# AirScout_SchematicsV2_0.net
KiCad netlist of a schematic drawn in Altium Designer
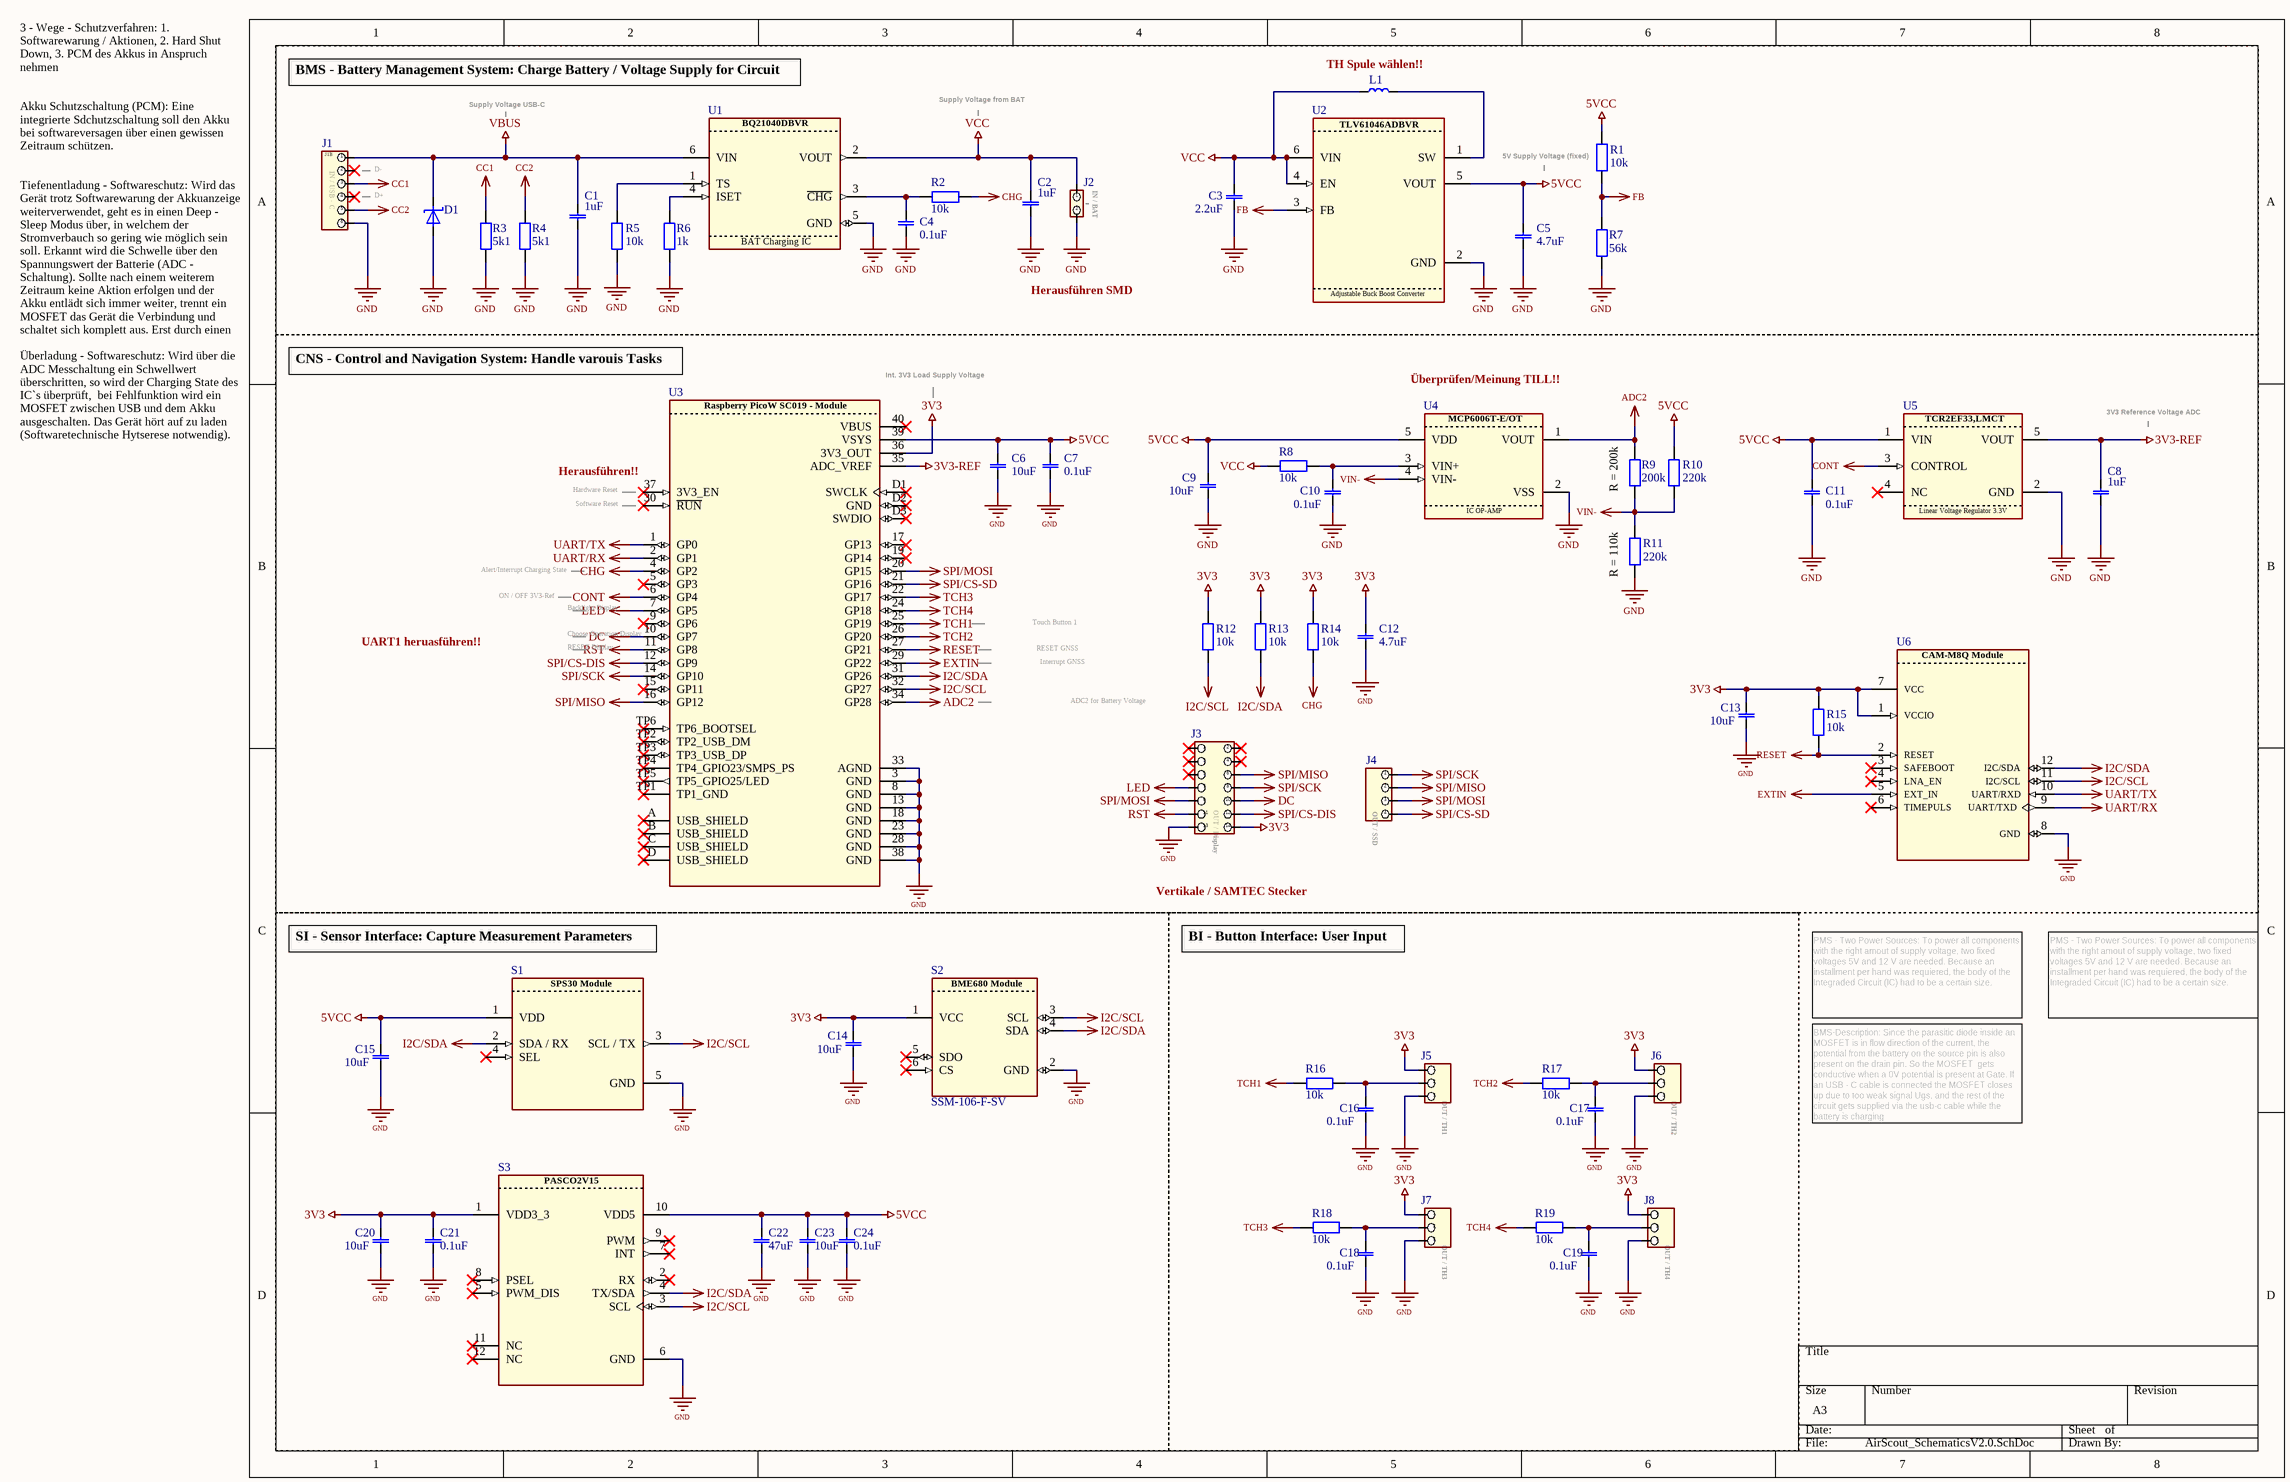
[diagram p0: AirScout_SchematicsV2.0.SchDoc]

(export (version "E")
  (design (tool "Eeschema 10.0.6"))
  (components
    (comp (ref "C1")
      (value "1uF")
      (footprint "CAPC340180_140N_KEM")
      (description "CAP CER 1UF 25V X7R 1206")
      (fields (field (name "Comment") "C1206C105K3RACTU"))
      (libsource (lib "AirScoutSchLibV2.0") (part "CAP"))
    )
    (comp (ref "C2")
      (value "1uF")
      (footprint "CAPC340180_140N_KEM")
      (description "CAP CER 1UF 25V X7R 1206")
      (fields (field (name "Comment") "C1206C105K3RACTU"))
      (libsource (lib "AirScoutSchLibV2.0") (part "CAP"))
    )
    (comp (ref "C3")
      (value "2.2uF")
      (footprint "CAPC340180_140N_KEM")
      (description "CAP CER 2.2UF 50V X7R 1206")
      (fields (field (name "Comment") "CL31B225KBHNNNE"))
      (libsource (lib "AirScoutSchLibV2.0") (part "CAP"))
    )
    (comp (ref "C4")
      (value "0.1uF")
      (footprint "CAPC340180_140N_KEM")
      (description "CAP CER 0.1UF 50V X7R 1206")
      (fields (field (name "Comment") "C1206C104K5RACTU"))
      (libsource (lib "AirScoutSchLibV2.0") (part "CAP"))
    )
    (comp (ref "C5")
      (value "4.7uF")
      (footprint "CAPC340180_140N_KEM")
      (description "CAP CER 4.7UF 50V X7R 1206")
      (fields (field (name "Comment") "CL31B475KBHNFNE"))
      (libsource (lib "AirScoutSchLibV2.0") (part "CAP"))
    )
    (comp (ref "C6")
      (value "10uF")
      (footprint "CAPC340180_140N_KEM")
      (description "CAP CER 10UF 25V X7R 1206")
      (fields (field (name "Comment") "CL31B106KAHNNNE"))
      (libsource (lib "AirScoutSchLibV2.0") (part "CAP"))
    )
    (comp (ref "C7")
      (value "0.1uF")
      (footprint "CAPC340180_140N_KEM")
      (description "CAP CER 0.1UF 50V X7R 1206")
      (fields (field (name "Comment") "C1206C104K5RACTU"))
      (libsource (lib "AirScoutSchLibV2.0") (part "CAP"))
    )
    (comp (ref "C8")
      (value "1uF")
      (footprint "CAPC340180_140N_KEM")
      (description "CAP CER 1UF 25V X7R 1206")
      (fields (field (name "Comment") "C1206C105K3RACTU"))
      (libsource (lib "AirScoutSchLibV2.0") (part "CAP"))
    )
    (comp (ref "C9")
      (value "10uF")
      (footprint "CAPC340180_140N_KEM")
      (description "CAP CER 10UF 25V X7R 1206")
      (fields (field (name "Comment") "CL31B106KAHNNNE"))
      (libsource (lib "AirScoutSchLibV2.0") (part "CAP"))
    )
    (comp (ref "C10")
      (value "0.1uF")
      (footprint "CAPC340180_140N_KEM")
      (description "CAP CER 0.1UF 50V X7R 1206")
      (fields (field (name "Comment") "C1206C104K5RACTU"))
      (libsource (lib "AirScoutSchLibV2.0") (part "CAP"))
    )
    (comp (ref "C11")
      (value "0.1uF")
      (footprint "CAPC340180_140N_KEM")
      (description "CAP CER 0.1UF 50V X7R 1206")
      (fields (field (name "Comment") "C1206C104K5RACTU"))
      (libsource (lib "AirScoutSchLibV2.0") (part "CAP"))
    )
    (comp (ref "C12")
      (value "4.7uF")
      (footprint "CAPC340180_140N_KEM")
      (description "CAP CER 4.7UF 50V X7R 1206")
      (fields (field (name "Comment") "CL31B475KBHNFNE"))
      (libsource (lib "AirScoutSchLibV2.0") (part "CAP"))
    )
    (comp (ref "C13")
      (value "10uF")
      (footprint "CAPC340180_140N_KEM")
      (description "CAP CER 10UF 25V X7R 1206")
      (fields (field (name "Comment") "CL31B106KAHNNNE"))
      (libsource (lib "AirScoutSchLibV2.0") (part "CAP"))
    )
    (comp (ref "C14")
      (value "10uF")
      (footprint "CAPC340180_140N_KEM")
      (description "CAP CER 10UF 25V X7R 1206")
      (fields (field (name "Comment") "CL31B106KAHNNNE"))
      (libsource (lib "AirScoutSchLibV2.0") (part "CAP"))
    )
    (comp (ref "C15")
      (value "10uF")
      (footprint "CAPC340180_140N_KEM")
      (description "CAP CER 10UF 25V X7R 1206")
      (fields (field (name "Comment") "CL31B106KAHNNNE"))
      (libsource (lib "AirScoutSchLibV2.0") (part "CAP"))
    )
    (comp (ref "C16")
      (value "0.1uF")
      (footprint "CAPC340180_140N_KEM")
      (description "CAP CER 0.1UF 50V X7R 1206")
      (fields (field (name "Comment") "C1206C104K5RACTU"))
      (libsource (lib "AirScoutSchLibV2.0") (part "CAP"))
    )
    (comp (ref "C17")
      (value "0.1uF")
      (footprint "CAPC340180_140N_KEM")
      (description "CAP CER 0.1UF 50V X7R 1206")
      (fields (field (name "Comment") "C1206C104K5RACTU"))
      (libsource (lib "AirScoutSchLibV2.0") (part "CAP"))
    )
    (comp (ref "C18")
      (value "0.1uF")
      (footprint "CAPC340180_140N_KEM")
      (description "CAP CER 0.1UF 50V X7R 1206")
      (fields (field (name "Comment") "C1206C104K5RACTU"))
      (libsource (lib "AirScoutSchLibV2.0") (part "CAP"))
    )
    (comp (ref "C19")
      (value "0.1uF")
      (footprint "CAPC340180_140N_KEM")
      (description "CAP CER 0.1UF 50V X7R 1206")
      (fields (field (name "Comment") "C1206C104K5RACTU"))
      (libsource (lib "AirScoutSchLibV2.0") (part "CAP"))
    )
    (comp (ref "C20")
      (value "10uF")
      (footprint "CAPC340180_140N_KEM")
      (description "CAP CER 10UF 25V X7R 1206")
      (fields (field (name "Comment") "CL31B106KAHNNNE"))
      (libsource (lib "AirScoutSchLibV2.0") (part "CAP"))
    )
    (comp (ref "C21")
      (value "0.1uF")
      (footprint "CAPC340180_140N_KEM")
      (description "CAP CER 0.1UF 50V X7R 1206")
      (fields (field (name "Comment") "C1206C104K5RACTU"))
      (libsource (lib "AirScoutSchLibV2.0") (part "CAP"))
    )
    (comp (ref "C22")
      (value "47uF")
      (footprint "CAPC340180_140N_KEM")
      (description "CAP CER 47UF 6.3V X5R 1206")
      (fields (field (name "Comment") "CL31A476MQHNNNE"))
      (libsource (lib "AirScoutSchLibV2.0") (part "CAP"))
    )
    (comp (ref "C23")
      (value "10uF")
      (footprint "CAPC340180_140N_KEM")
      (description "CAP CER 10UF 25V X7R 1206")
      (fields (field (name "Comment") "CL31B106KAHNNNE"))
      (libsource (lib "AirScoutSchLibV2.0") (part "CAP"))
    )
    (comp (ref "C24")
      (value "0.1uF")
      (footprint "CAPC340180_140N_KEM")
      (description "CAP CER 0.1UF 50V X7R 1206")
      (fields (field (name "Comment") "C1206C104K5RACTU"))
      (libsource (lib "AirScoutSchLibV2.0") (part "CAP"))
    )
    (comp (ref "D1")
      (value "SMBJ14CA-13-F")
      (footprint "SMB_DIO")
      (description "TVS DIODE 14VWM 23.2VC SMB")
      (libsource (lib "AirScoutSchLibV2.0") (part "Diode-Schottky"))
    )
    (comp (ref "J1")
      (value "B6B-PH-K-S")
      (footprint "JST_B6B-PH-K-S")
      (description "CONN HEADER VERT 6POS 2MM")
      (libsource (lib "AirScoutSchLibV2.0") (part "CON6x1"))
    )
    (comp (ref "J2")
      (value "B02B-PASK-1")
      (footprint "JST_B2B-PH-K-S")
      (description "CONN HEADER VERT 2POS 2MM")
      (libsource (lib "AirScoutSchLibV2.0") (part "CON2x1_vertical"))
    )
    (comp (ref "J3")
      (value "0705430013")
      (footprint "CONN_14POL_SAMTEC")
      (description "CONN HEADER VERT 14POS 2.54MM")
      (libsource (lib "AirScoutSchLibV2.0") (part "CON7x2"))
    )
    (comp (ref "J4")
      (value "4x1 vertical Connector Box")
      (footprint "JST_B4B-XH-A")
      (description "Can be used to create connectivity between two plates with cables or similar.")
      (libsource (lib "AirScoutSchLibV2.0") (part "CON 4x1"))
    )
    (comp (ref "J5")
      (value "0705430002")
      (footprint "CONN_3POL_SAMTEC")
      (description "CONN HEADER VERT 3POS 2.54MM")
      (libsource (lib "AirScoutSchLibV2.0") (part "CON 3x1"))
    )
    (comp (ref "J6")
      (value "0705430002")
      (footprint "CONN_3POL_SAMTEC")
      (description "CONN HEADER VERT 3POS 2.54MM")
      (libsource (lib "AirScoutSchLibV2.0") (part "CON 3x1"))
    )
    (comp (ref "J7")
      (value "0705430002")
      (footprint "CONN_3POL_SAMTEC")
      (description "CONN HEADER VERT 3POS 2.54MM")
      (libsource (lib "AirScoutSchLibV2.0") (part "CON 3x1"))
    )
    (comp (ref "J8")
      (value "0705430002")
      (footprint "CONN_3POL_SAMTEC")
      (description "CONN HEADER VERT 3POS 2.54MM")
      (libsource (lib "AirScoutSchLibV2.0") (part "CON 3x1"))
    )
    (comp (ref "L1")
      (value "PA4332.103NLT")
      (footprint "IND_FDSD0420-H-100M=P3")
      (description "FIXED IND 10UH 2A 216 MOHM SMD; \r\nAIUR-05-100K")
      (libsource (lib "AirScoutSchLibV2.0") (part "Inductor"))
    )
    (comp (ref "R1")
      (value "10k")
      (footprint "RESC3116X65N")
      (description "RES 10K OHM 1% 1/4W 1206")
      (fields (field (name "Comment") "RC1206FR-0710KL"))
      (libsource (lib "AirScoutSchLibV2.0") (part "RES"))
    )
    (comp (ref "R2")
      (value "10k")
      (footprint "RESC3116X65N")
      (description "RES 10K OHM 1% 1/4W 1206")
      (fields (field (name "Comment") "RC1206FR-0710KL"))
      (libsource (lib "AirScoutSchLibV2.0") (part "RES"))
    )
    (comp (ref "R3")
      (value "5k1")
      (footprint "RESC3116X65N")
      (description "RES 5.1K OHM 5% 1/4W 1206")
      (fields (field (name "Comment") "RMCF1206JT5K10"))
      (libsource (lib "AirScoutSchLibV2.0") (part "RES"))
    )
    (comp (ref "R4")
      (value "5k1")
      (footprint "RESC3116X65N")
      (description "RES 5.1K OHM 5% 1/4W 1206")
      (fields (field (name "Comment") "RMCF1206JT5K10"))
      (libsource (lib "AirScoutSchLibV2.0") (part "RES"))
    )
    (comp (ref "R5")
      (value "10k")
      (footprint "RESC3116X65N")
      (description "RES 10K OHM 1% 1/4W 1206")
      (fields (field (name "Comment") "RC1206FR-0710KL"))
      (libsource (lib "AirScoutSchLibV2.0") (part "RES"))
    )
    (comp (ref "R6")
      (value "1k")
      (footprint "RESC3116X65N")
      (description "RES 1K OHM 1% 1/2W 1206")
      (fields (field (name "Comment") "RNCP1206FTD1K00"))
      (libsource (lib "AirScoutSchLibV2.0") (part "RES"))
    )
    (comp (ref "R7")
      (value "56k")
      (footprint "RESC3116X65N")
      (description "RES 56K OHM 5% 1/4W 1206")
      (fields (field (name "Comment") "RMCF1206JT56K0"))
      (libsource (lib "AirScoutSchLibV2.0") (part "RES"))
    )
    (comp (ref "R8")
      (value "10k")
      (footprint "RESC3116X65N")
      (description "RES 10K OHM 1% 1/4W 1206")
      (fields (field (name "Comment") "RC1206FR-0710KL"))
      (libsource (lib "AirScoutSchLibV2.0") (part "RES"))
    )
    (comp (ref "R9")
      (value "200k")
      (footprint "RESC3116X65N")
      (description "RES 200K OHM 5% 1/4W 1206")
      (fields (field (name "Comment") "RC1206JR-07200KL"))
      (libsource (lib "AirScoutSchLibV2.0") (part "RES"))
    )
    (comp (ref "R10")
      (value "220k")
      (footprint "RESC3116X65N")
      (description "RES 220K OHM 5% 1/4W 1206")
      (fields (field (name "Comment") "RC1206JR-07220KL"))
      (libsource (lib "AirScoutSchLibV2.0") (part "RES"))
    )
    (comp (ref "R11")
      (value "220k")
      (footprint "RESC3116X65N")
      (description "RES 220K OHM 5% 1/4W 1206")
      (fields (field (name "Comment") "RC1206JR-07220KL"))
      (libsource (lib "AirScoutSchLibV2.0") (part "RES"))
    )
    (comp (ref "R12")
      (value "10k")
      (footprint "RESC3116X65N")
      (description "RES 10K OHM 1% 1/4W 1206")
      (fields (field (name "Comment") "RC1206FR-0710KL"))
      (libsource (lib "AirScoutSchLibV2.0") (part "RES"))
    )
    (comp (ref "R13")
      (value "10k")
      (footprint "RESC3116X65N")
      (description "RES 10K OHM 1% 1/4W 1206")
      (fields (field (name "Comment") "RC1206FR-0710KL"))
      (libsource (lib "AirScoutSchLibV2.0") (part "RES"))
    )
    (comp (ref "R14")
      (value "10k")
      (footprint "RESC3116X65N")
      (description "RES 10K OHM 1% 1/4W 1206")
      (fields (field (name "Comment") "RC1206FR-0710KL"))
      (libsource (lib "AirScoutSchLibV2.0") (part "RES"))
    )
    (comp (ref "R15")
      (value "10k")
      (footprint "RESC3116X65N")
      (description "RES 10K OHM 1% 1/4W 1206")
      (fields (field (name "Comment") "RC1206FR-0710KL"))
      (libsource (lib "AirScoutSchLibV2.0") (part "RES"))
    )
    (comp (ref "R16")
      (value "10k")
      (footprint "RESC3116X65N")
      (description "RES 10K OHM 1% 1/4W 1206")
      (fields (field (name "Comment") "RC1206FR-0710KL"))
      (libsource (lib "AirScoutSchLibV2.0") (part "RES"))
    )
    (comp (ref "R17")
      (value "10k")
      (footprint "RESC3116X65N")
      (description "RES 10K OHM 1% 1/4W 1206")
      (fields (field (name "Comment") "RC1206FR-0710KL"))
      (libsource (lib "AirScoutSchLibV2.0") (part "RES"))
    )
    (comp (ref "R18")
      (value "10k")
      (footprint "RESC3116X65N")
      (description "RES 10K OHM 1% 1/4W 1206")
      (fields (field (name "Comment") "RC1206FR-0710KL"))
      (libsource (lib "AirScoutSchLibV2.0") (part "RES"))
    )
    (comp (ref "R19")
      (value "10k")
      (footprint "RESC3116X65N")
      (description "RES 10K OHM 1% 1/4W 1206")
      (fields (field (name "Comment") "RC1206FR-0710KL"))
      (libsource (lib "AirScoutSchLibV2.0") (part "RES"))
    )
    (comp (ref "S1")
      (value "B5B-ZR")
      (footprint "CONN5_B5B-ZR_JST")
      (description "Plug: CONN HEADER VERT 5POS 1.5MM; Air Sensor Dust Sensor Box SPS30 Module: 1649-1106-ND")
      (libsource (lib "AirScoutSchLibV2.0") (part "SPS30 Module"))
    )
    (comp (ref "S2")
      (value "SSM-106-F-SV")
      (footprint "PIM357")
      (libsource (lib "AirScoutSchLibV2.0") (part "BME680 Module"))
    )
    (comp (ref "S3")
      (value "SSM-106-F-SV")
      (footprint "IFX-SMD-LG-MLGA-14-1-V_MODUL")
      (description "(2x) CONN RCPT 6POS 0.1 GOLD SMD; Sensor: EVALCO25VMINIBOARDTOBO1; EVAL BOARD")
      (libsource (lib "AirScoutSchLibV2.0") (part "PASCO2V15 Module"))
    )
    (comp (ref "U1")
      (value "BQ21040DBVR")
      (footprint "SOT95P280X145-6N")
      (fields (field (name "MF") "Texas Instruments"))
      (libsource (lib "AirScoutSchLibV2.0") (part "BQ21040DBVR"))
    )
    (comp (ref "U2")
      (value "TLV61046ADBVR")
      (footprint "DBV0006A_M")
      (description "28-V Output Voltage Boost Converter with Power Diode and Isolation Switch 6-SOT-23 -40 to 125")
      (fields (field (name "COPYRIGHT") "Copyright (C) 2025 Ultra Librarian. All rights reserved."))
      (libsource (lib "AirScoutSchLibV2.0") (part "TLV61046ADBVR"))
    )
    (comp (ref "U3")
      (value "SSM-120-L-SV-BE-K-TR")
      (footprint "PicoW SC019")
      (description "(2x) CONN RCPT 20POS 0.1 GOLD SMD; PicoW: SC0918; RASPBERRY PI PICO W RP2040")
      (libsource (lib "AirScoutSchLibV2.0") (part "Raspberry PicoW SC019 Module"))
    )
    (comp (ref "U4")
      (value "MCP6006T-E/OT")
      (footprint "SOT23-5-AP2202K_DIO-M")
      (description "IC OPAMP GP 1 CIRCUIT SOT23-5")
      (libsource (lib "AirScoutSchLibV2.0") (part "MCP6006T-E/OT"))
    )
    (comp (ref "U5")
      (value "TCR2EF33,LM(CT")
      (footprint "SOT-25   SMV_TOS")
      (description "IC REG LINEAR 3.3V 200MA SMV")
      (fields (field (name "COPYRIGHT") "Copyright (C) 2025 Ultra Librarian. All rights reserved."))
      (libsource (lib "AirScoutSchLibV2.0") (part "TCR2EF33,LMCT"))
    )
    (comp (ref "U6")
      (value "FM20206VBNN; SSM-106-F-SV")
      (footprint "CAM8MQ-Mod")
      (description "(2x) RECEPTACLE, SMT, SINGLE ROW, .10; GPS - Module:  201880; CAM-M8Q-BREAKOUT MULTI GNSS MODU")
      (libsource (lib "AirScoutSchLibV2.0") (part "CAM-M8Q Module"))
    )
  )
  (nets
    (net (code "1") (name "3V3") (class "Default")
      (node (ref "C12") (pin "2") (pinfunction "2_2") (pintype "passive"))
      (node (ref "C13") (pin "2") (pinfunction "2_2") (pintype "passive"))
      (node (ref "C14") (pin "2") (pinfunction "2_2") (pintype "passive"))
      (node (ref "C20") (pin "2") (pinfunction "2_2") (pintype "passive"))
      (node (ref "C21") (pin "2") (pinfunction "2_2") (pintype "passive"))
      (node (ref "J3") (pin "14") (pinfunction "14_14") (pintype "passive"))
      (node (ref "J5") (pin "1") (pinfunction "1_1") (pintype "passive"))
      (node (ref "J6") (pin "1") (pinfunction "1_1") (pintype "passive"))
      (node (ref "J7") (pin "1") (pinfunction "1_1") (pintype "passive"))
      (node (ref "J8") (pin "1") (pinfunction "1_1") (pintype "passive"))
      (node (ref "R12") (pin "2") (pinfunction "2_2") (pintype "passive"))
      (node (ref "R13") (pin "2") (pinfunction "2_2") (pintype "passive"))
      (node (ref "R14") (pin "2") (pinfunction "2_2") (pintype "passive"))
      (node (ref "R15") (pin "2") (pinfunction "2_2") (pintype "passive"))
      (node (ref "S2") (pin "1") (pinfunction "VCC_1") (pintype "power_in"))
      (node (ref "S3") (pin "1") (pinfunction "VDD3_3_1") (pintype "power_in"))
      (node (ref "U3") (pin "36") (pinfunction "3V3_OUT_36") (pintype "power_in"))
      (node (ref "U6") (pin "1") (pinfunction "VCCIO_1") (pintype "input"))
      (node (ref "U6") (pin "7") (pinfunction "VCC_7") (pintype "power_in"))
    )
    (net (code "2") (name "3V3-REF") (class "Default")
      (node (ref "C8") (pin "2") (pinfunction "2_2") (pintype "passive"))
      (node (ref "U3") (pin "35") (pinfunction "ADC_VREF_35") (pintype "power_in"))
      (node (ref "U5") (pin "5") (pinfunction "VOUT_5") (pintype "power_in"))
    )
    (net (code "3") (name "5VCC") (class "Default")
      (node (ref "C11") (pin "2") (pinfunction "2_2") (pintype "passive"))
      (node (ref "C15") (pin "2") (pinfunction "2_2") (pintype "passive"))
      (node (ref "C22") (pin "2") (pinfunction "2_2") (pintype "passive"))
      (node (ref "C23") (pin "2") (pinfunction "2_2") (pintype "passive"))
      (node (ref "C24") (pin "2") (pinfunction "2_2") (pintype "passive"))
      (node (ref "C5") (pin "2") (pinfunction "2_2") (pintype "passive"))
      (node (ref "C6") (pin "2") (pinfunction "2_2") (pintype "passive"))
      (node (ref "C7") (pin "2") (pinfunction "2_2") (pintype "passive"))
      (node (ref "C9") (pin "2") (pinfunction "2_2") (pintype "passive"))
      (node (ref "R1") (pin "2") (pinfunction "2_2") (pintype "passive"))
      (node (ref "R10") (pin "2") (pinfunction "2_2") (pintype "passive"))
      (node (ref "S1") (pin "1") (pinfunction "VDD_1") (pintype "passive"))
      (node (ref "S3") (pin "10") (pinfunction "VDD5_10") (pintype "power_in"))
      (node (ref "U2") (pin "5") (pinfunction "VOUT_5") (pintype "power_in"))
      (node (ref "U3") (pin "39") (pinfunction "VSYS_39") (pintype "power_in"))
      (node (ref "U4") (pin "5") (pinfunction "VDD_5") (pintype "power_in"))
      (node (ref "U5") (pin "1") (pinfunction "VIN_1") (pintype "power_in"))
    )
    (net (code "4") (name "ADC2") (class "Default")
      (node (ref "R9") (pin "2") (pinfunction "2_2") (pintype "passive"))
      (node (ref "U3") (pin "34") (pinfunction "GP28_34") (pintype "bidirectional"))
      (node (ref "U4") (pin "1") (pinfunction "VOUT_1") (pintype "power_in"))
    )
    (net (code "5") (name "CC1") (class "Default")
      (node (ref "J1") (pin "3") (pinfunction "3_3") (pintype "passive"))
      (node (ref "R3") (pin "2") (pinfunction "2_2") (pintype "passive"))
    )
    (net (code "6") (name "CC2") (class "Default")
      (node (ref "J1") (pin "5") (pinfunction "5_5") (pintype "passive"))
      (node (ref "R4") (pin "2") (pinfunction "2_2") (pintype "passive"))
    )
    (net (code "7") (name "CHG") (class "Default")
      (node (ref "R14") (pin "1") (pinfunction "1_1") (pintype "passive"))
      (node (ref "R2") (pin "1") (pinfunction "1_1") (pintype "passive"))
      (node (ref "U3") (pin "4") (pinfunction "GP2_4") (pintype "bidirectional"))
    )
    (net (code "8") (name "CONT") (class "Default")
      (node (ref "U3") (pin "6") (pinfunction "GP4_6") (pintype "bidirectional"))
      (node (ref "U5") (pin "3") (pinfunction "CONTROL_3") (pintype "input"))
    )
    (net (code "9") (name "DC") (class "Default")
      (node (ref "J3") (pin "10") (pinfunction "10_10") (pintype "passive"))
      (node (ref "U3") (pin "10") (pinfunction "GP7_10") (pintype "bidirectional"))
    )
    (net (code "10") (name "EXTIN") (class "Default")
      (node (ref "U3") (pin "29") (pinfunction "GP22_29") (pintype "bidirectional"))
      (node (ref "U6") (pin "5") (pinfunction "EXT_IN_5") (pintype "input"))
    )
    (net (code "11") (name "FB") (class "Default")
      (node (ref "R1") (pin "1") (pinfunction "1_1") (pintype "passive"))
      (node (ref "R7") (pin "2") (pinfunction "2_2") (pintype "passive"))
      (node (ref "U2") (pin "3") (pinfunction "FB_3") (pintype "input"))
    )
    (net (code "12") (name "GND") (class "Default")
      (node (ref "C1") (pin "1") (pinfunction "1_1") (pintype "passive"))
      (node (ref "C10") (pin "1") (pinfunction "1_1") (pintype "passive"))
      (node (ref "C11") (pin "1") (pinfunction "1_1") (pintype "passive"))
      (node (ref "C12") (pin "1") (pinfunction "1_1") (pintype "passive"))
      (node (ref "C13") (pin "1") (pinfunction "1_1") (pintype "passive"))
      (node (ref "C14") (pin "1") (pinfunction "1_1") (pintype "passive"))
      (node (ref "C15") (pin "1") (pinfunction "1_1") (pintype "passive"))
      (node (ref "C16") (pin "1") (pinfunction "1_1") (pintype "passive"))
      (node (ref "C17") (pin "1") (pinfunction "1_1") (pintype "passive"))
      (node (ref "C18") (pin "1") (pinfunction "1_1") (pintype "passive"))
      (node (ref "C19") (pin "1") (pinfunction "1_1") (pintype "passive"))
      (node (ref "C2") (pin "1") (pinfunction "1_1") (pintype "passive"))
      (node (ref "C20") (pin "1") (pinfunction "1_1") (pintype "passive"))
      (node (ref "C21") (pin "1") (pinfunction "1_1") (pintype "passive"))
      (node (ref "C22") (pin "1") (pinfunction "1_1") (pintype "passive"))
      (node (ref "C23") (pin "1") (pinfunction "1_1") (pintype "passive"))
      (node (ref "C24") (pin "1") (pinfunction "1_1") (pintype "passive"))
      (node (ref "C3") (pin "1") (pinfunction "1_1") (pintype "passive"))
      (node (ref "C4") (pin "1") (pinfunction "1_1") (pintype "passive"))
      (node (ref "C5") (pin "1") (pinfunction "1_1") (pintype "passive"))
      (node (ref "C6") (pin "1") (pinfunction "1_1") (pintype "passive"))
      (node (ref "C7") (pin "1") (pinfunction "1_1") (pintype "passive"))
      (node (ref "C8") (pin "1") (pinfunction "1_1") (pintype "passive"))
      (node (ref "C9") (pin "1") (pinfunction "1_1") (pintype "passive"))
      (node (ref "D1") (pin "A") (pinfunction "A_A") (pintype "passive"))
      (node (ref "J1") (pin "6") (pinfunction "6_6") (pintype "passive"))
      (node (ref "J2") (pin "2") (pinfunction "-_2") (pintype "passive"))
      (node (ref "J3") (pin "13") (pinfunction "13_13") (pintype "passive"))
      (node (ref "J5") (pin "3") (pinfunction "3_3") (pintype "passive"))
      (node (ref "J6") (pin "3") (pinfunction "3_3") (pintype "passive"))
      (node (ref "J7") (pin "3") (pinfunction "3_3") (pintype "passive"))
      (node (ref "J8") (pin "3") (pinfunction "3_3") (pintype "passive"))
      (node (ref "R11") (pin "1") (pinfunction "1_1") (pintype "passive"))
      (node (ref "R3") (pin "1") (pinfunction "1_1") (pintype "passive"))
      (node (ref "R4") (pin "1") (pinfunction "1_1") (pintype "passive"))
      (node (ref "R5") (pin "1") (pinfunction "1_1") (pintype "passive"))
      (node (ref "R6") (pin "1") (pinfunction "1_1") (pintype "passive"))
      (node (ref "R7") (pin "1") (pinfunction "1_1") (pintype "passive"))
      (node (ref "S1") (pin "5") (pinfunction "GND_5") (pintype "passive"))
      (node (ref "S2") (pin "2") (pinfunction "GND_2") (pintype "bidirectional"))
      (node (ref "S3") (pin "6") (pinfunction "GND_6") (pintype "power_in"))
      (node (ref "U1") (pin "5") (pinfunction "GND_5") (pintype "bidirectional"))
      (node (ref "U2") (pin "2") (pinfunction "GND_2") (pintype "power_in"))
      (node (ref "U3") (pin "13") (pinfunction "GND_13") (pintype "power_in"))
      (node (ref "U3") (pin "18") (pinfunction "GND_18") (pintype "power_in"))
      (node (ref "U3") (pin "23") (pinfunction "GND_23") (pintype "power_in"))
      (node (ref "U3") (pin "28") (pinfunction "GND_28") (pintype "power_in"))
      (node (ref "U3") (pin "3") (pinfunction "GND_3") (pintype "power_in"))
      (node (ref "U3") (pin "33") (pinfunction "AGND_33") (pintype "power_in"))
      (node (ref "U3") (pin "38") (pinfunction "GND_38") (pintype "power_in"))
      (node (ref "U3") (pin "8") (pinfunction "GND_8") (pintype "power_in"))
      (node (ref "U4") (pin "2") (pinfunction "VSS_2") (pintype "power_in"))
      (node (ref "U5") (pin "2") (pinfunction "GND_2") (pintype "power_in"))
      (node (ref "U6") (pin "8") (pinfunction "GND_8") (pintype "bidirectional"))
    )
    (net (code "13") (name "I2C{slash}SCL") (class "Default")
      (node (ref "R12") (pin "1") (pinfunction "1_1") (pintype "passive"))
      (node (ref "S1") (pin "3") (pinfunction "SCL_/_TX_3") (pintype "output"))
      (node (ref "S2") (pin "3") (pinfunction "SCL_3") (pintype "bidirectional"))
      (node (ref "S3") (pin "3") (pinfunction "SCL_3") (pintype "bidirectional"))
      (node (ref "U3") (pin "32") (pinfunction "GP27_32") (pintype "bidirectional"))
      (node (ref "U6") (pin "11") (pinfunction "I2C/SCL_11") (pintype "bidirectional"))
    )
    (net (code "14") (name "I2C{slash}SDA") (class "Default")
      (node (ref "R13") (pin "1") (pinfunction "1_1") (pintype "passive"))
      (node (ref "S1") (pin "2") (pinfunction "SDA_/_RX_2") (pintype "input"))
      (node (ref "S2") (pin "4") (pinfunction "SDA_4") (pintype "bidirectional"))
      (node (ref "S3") (pin "4") (pinfunction "TX/SDA_4") (pintype "output"))
      (node (ref "U3") (pin "31") (pinfunction "GP26_31") (pintype "bidirectional"))
      (node (ref "U6") (pin "12") (pinfunction "I2C/SDA_12") (pintype "bidirectional"))
    )
    (net (code "15") (name "LED") (class "Default")
      (node (ref "J3") (pin "7") (pinfunction "7_7") (pintype "passive"))
      (node (ref "U3") (pin "7") (pinfunction "GP5_7") (pintype "bidirectional"))
    )
    (net (code "16") (name "Net-(C16-Pad2)") (class "Default")
      (node (ref "C16") (pin "2") (pinfunction "2_2") (pintype "passive"))
      (node (ref "J5") (pin "2") (pinfunction "2_2") (pintype "passive"))
      (node (ref "R16") (pin "1") (pinfunction "1_1") (pintype "passive"))
    )
    (net (code "17") (name "Net-(C17-Pad2)") (class "Default")
      (node (ref "C17") (pin "2") (pinfunction "2_2") (pintype "passive"))
      (node (ref "J6") (pin "2") (pinfunction "2_2") (pintype "passive"))
      (node (ref "R17") (pin "1") (pinfunction "1_1") (pintype "passive"))
    )
    (net (code "18") (name "Net-(C18-Pad2)") (class "Default")
      (node (ref "C18") (pin "2") (pinfunction "2_2") (pintype "passive"))
      (node (ref "J7") (pin "2") (pinfunction "2_2") (pintype "passive"))
      (node (ref "R18") (pin "1") (pinfunction "1_1") (pintype "passive"))
    )
    (net (code "19") (name "Net-(C19-Pad2)") (class "Default")
      (node (ref "C19") (pin "2") (pinfunction "2_2") (pintype "passive"))
      (node (ref "J8") (pin "2") (pinfunction "2_2") (pintype "passive"))
      (node (ref "R19") (pin "1") (pinfunction "1_1") (pintype "passive"))
    )
    (net (code "20") (name "Net-(U1-ISET)") (class "Default")
      (node (ref "R6") (pin "2") (pinfunction "2_2") (pintype "passive"))
      (node (ref "U1") (pin "4") (pinfunction "ISET_4") (pintype "input"))
    )
    (net (code "21") (name "Net-(U1-TS)") (class "Default")
      (node (ref "R5") (pin "2") (pinfunction "2_2") (pintype "passive"))
      (node (ref "U1") (pin "1") (pinfunction "TS_1") (pintype "input"))
    )
    (net (code "22") (name "Net-(U1-~{CHG})") (class "Default")
      (node (ref "C4") (pin "2") (pinfunction "2_2") (pintype "passive"))
      (node (ref "R2") (pin "2") (pinfunction "2_2") (pintype "passive"))
      (node (ref "U1") (pin "3") (pinfunction "~{CHG}_3") (pintype "output"))
    )
    (net (code "23") (name "Net-(U2-SW)") (class "Default")
      (node (ref "L1") (pin "2") (pinfunction "2_2") (pintype "passive"))
      (node (ref "U2") (pin "1") (pinfunction "SW_1") (pintype "power_in"))
    )
    (net (code "24") (name "Net-(U4-VIN+)") (class "Default")
      (node (ref "C10") (pin "2") (pinfunction "2_2") (pintype "passive"))
      (node (ref "R8") (pin "1") (pinfunction "1_1") (pintype "passive"))
      (node (ref "U4") (pin "3") (pinfunction "VIN+_3") (pintype "input"))
    )
    (net (code "25") (name "RESET") (class "Default")
      (node (ref "R15") (pin "1") (pinfunction "1_1") (pintype "passive"))
      (node (ref "U3") (pin "27") (pinfunction "GP21_27") (pintype "bidirectional"))
      (node (ref "U6") (pin "2") (pinfunction "RESET_2") (pintype "input"))
    )
    (net (code "26") (name "RST") (class "Default")
      (node (ref "J3") (pin "11") (pinfunction "11_11") (pintype "passive"))
      (node (ref "U3") (pin "11") (pinfunction "GP8_11") (pintype "bidirectional"))
    )
    (net (code "27") (name "SPI{slash}CS-DIS") (class "Default")
      (node (ref "J3") (pin "12") (pinfunction "12_12") (pintype "passive"))
      (node (ref "U3") (pin "12") (pinfunction "GP9_12") (pintype "bidirectional"))
    )
    (net (code "28") (name "SPI{slash}CS-SD") (class "Default")
      (node (ref "J4") (pin "4") (pinfunction "4_4") (pintype "passive"))
      (node (ref "U3") (pin "21") (pinfunction "GP16_21") (pintype "bidirectional"))
    )
    (net (code "29") (name "SPI{slash}MISO") (class "Default")
      (node (ref "J3") (pin "6") (pinfunction "6_6") (pintype "passive"))
      (node (ref "J4") (pin "2") (pinfunction "2_2") (pintype "passive"))
      (node (ref "U3") (pin "16") (pinfunction "GP12_16") (pintype "bidirectional"))
    )
    (net (code "30") (name "SPI{slash}MOSI") (class "Default")
      (node (ref "J3") (pin "9") (pinfunction "9_9") (pintype "passive"))
      (node (ref "J4") (pin "3") (pinfunction "3_3") (pintype "passive"))
      (node (ref "U3") (pin "20") (pinfunction "GP15_20") (pintype "bidirectional"))
    )
    (net (code "31") (name "SPI{slash}SCK") (class "Default")
      (node (ref "J3") (pin "8") (pinfunction "8_8") (pintype "passive"))
      (node (ref "J4") (pin "1") (pinfunction "1_1") (pintype "passive"))
      (node (ref "U3") (pin "14") (pinfunction "GP10_14") (pintype "bidirectional"))
    )
    (net (code "32") (name "TCH1") (class "Default")
      (node (ref "R16") (pin "2") (pinfunction "2_2") (pintype "passive"))
      (node (ref "U3") (pin "25") (pinfunction "GP19_25") (pintype "bidirectional"))
    )
    (net (code "33") (name "TCH2") (class "Default")
      (node (ref "R17") (pin "2") (pinfunction "2_2") (pintype "passive"))
      (node (ref "U3") (pin "26") (pinfunction "GP20_26") (pintype "bidirectional"))
    )
    (net (code "34") (name "TCH3") (class "Default")
      (node (ref "R18") (pin "2") (pinfunction "2_2") (pintype "passive"))
      (node (ref "U3") (pin "22") (pinfunction "GP17_22") (pintype "bidirectional"))
    )
    (net (code "35") (name "TCH4") (class "Default")
      (node (ref "R19") (pin "2") (pinfunction "2_2") (pintype "passive"))
      (node (ref "U3") (pin "24") (pinfunction "GP18_24") (pintype "bidirectional"))
    )
    (net (code "36") (name "UART{slash}RX") (class "Default")
      (node (ref "U3") (pin "2") (pinfunction "GP1_2") (pintype "bidirectional"))
      (node (ref "U6") (pin "9") (pinfunction "UART/TXD_9") (pintype "output"))
    )
    (net (code "37") (name "UART{slash}TX") (class "Default")
      (node (ref "U3") (pin "1") (pinfunction "GP0_1") (pintype "bidirectional"))
      (node (ref "U6") (pin "10") (pinfunction "UART/RXD_10") (pintype "input"))
    )
    (net (code "38") (name "VBUS") (class "Default")
      (node (ref "C1") (pin "2") (pinfunction "2_2") (pintype "passive"))
      (node (ref "D1") (pin "K") (pinfunction "K_K") (pintype "passive"))
      (node (ref "J1") (pin "1") (pinfunction "1_1") (pintype "passive"))
      (node (ref "U1") (pin "6") (pinfunction "VIN_6") (pintype "power_in"))
    )
    (net (code "39") (name "VCC") (class "Default")
      (node (ref "C2") (pin "2") (pinfunction "2_2") (pintype "passive"))
      (node (ref "C3") (pin "2") (pinfunction "2_2") (pintype "passive"))
      (node (ref "J2") (pin "1") (pinfunction "+_1") (pintype "passive"))
      (node (ref "L1") (pin "1") (pinfunction "1_1") (pintype "passive"))
      (node (ref "R8") (pin "2") (pinfunction "2_2") (pintype "passive"))
      (node (ref "U1") (pin "2") (pinfunction "VOUT_2") (pintype "output"))
      (node (ref "U2") (pin "4") (pinfunction "EN_4") (pintype "input"))
      (node (ref "U2") (pin "6") (pinfunction "VIN_6") (pintype "power_in"))
    )
    (net (code "40") (name "VIN-") (class "Default")
      (node (ref "R10") (pin "1") (pinfunction "1_1") (pintype "passive"))
      (node (ref "R11") (pin "2") (pinfunction "2_2") (pintype "passive"))
      (node (ref "R9") (pin "1") (pinfunction "1_1") (pintype "passive"))
      (node (ref "U4") (pin "4") (pinfunction "VIN-_4") (pintype "input"))
    )
    (net (code "41") (name "unconnected-(J1-Pad2)") (class "Default")
      (node (ref "J1") (pin "2") (pinfunction "2_2") (pintype "passive+no_connect"))
    )
    (net (code "42") (name "unconnected-(J1-Pad4)") (class "Default")
      (node (ref "J1") (pin "4") (pinfunction "4_4") (pintype "passive+no_connect"))
    )
    (net (code "43") (name "unconnected-(J3-Pad1)") (class "Default")
      (node (ref "J3") (pin "1") (pinfunction "1_1") (pintype "passive+no_connect"))
    )
    (net (code "44") (name "unconnected-(J3-Pad2)") (class "Default")
      (node (ref "J3") (pin "2") (pinfunction "2_2") (pintype "passive+no_connect"))
    )
    (net (code "45") (name "unconnected-(J3-Pad3)") (class "Default")
      (node (ref "J3") (pin "3") (pinfunction "3_3") (pintype "passive+no_connect"))
    )
    (net (code "46") (name "unconnected-(J3-Pad4)") (class "Default")
      (node (ref "J3") (pin "4") (pinfunction "4_4") (pintype "passive+no_connect"))
    )
    (net (code "47") (name "unconnected-(J3-Pad5)") (class "Default")
      (node (ref "J3") (pin "5") (pinfunction "5_5") (pintype "passive+no_connect"))
    )
    (net (code "48") (name "unconnected-(S1-SEL-Pad4)") (class "Default")
      (node (ref "S1") (pin "4") (pinfunction "SEL_4") (pintype "input+no_connect"))
    )
    (net (code "49") (name "unconnected-(S2-CS-Pad6)") (class "Default")
      (node (ref "S2") (pin "6") (pinfunction "CS_6") (pintype "input+no_connect"))
    )
    (net (code "50") (name "unconnected-(S2-SDO-Pad5)") (class "Default")
      (node (ref "S2") (pin "5") (pinfunction "SDO_5") (pintype "bidirectional+no_connect"))
    )
    (net (code "51") (name "unconnected-(S3-INT-Pad7)") (class "Default")
      (node (ref "S3") (pin "7") (pinfunction "INT_7") (pintype "output+no_connect"))
    )
    (net (code "52") (name "unconnected-(S3-NC-Pad11)") (class "Default")
      (node (ref "S3") (pin "11") (pinfunction "NC_11") (pintype "power_in+no_connect"))
    )
    (net (code "53") (name "unconnected-(S3-NC-Pad12)") (class "Default")
      (node (ref "S3") (pin "12") (pinfunction "NC_12") (pintype "passive+no_connect"))
    )
    (net (code "54") (name "unconnected-(S3-PSEL-Pad8)") (class "Default")
      (node (ref "S3") (pin "8") (pinfunction "PSEL_8") (pintype "input+no_connect"))
    )
    (net (code "55") (name "unconnected-(S3-PWM-Pad9)") (class "Default")
      (node (ref "S3") (pin "9") (pinfunction "PWM_9") (pintype "output+no_connect"))
    )
    (net (code "56") (name "unconnected-(S3-PWM_DIS-Pad5)") (class "Default")
      (node (ref "S3") (pin "5") (pinfunction "PWM_DIS_5") (pintype "input+no_connect"))
    )
    (net (code "57") (name "unconnected-(S3-RX-Pad2)") (class "Default")
      (node (ref "S3") (pin "2") (pinfunction "RX_2") (pintype "bidirectional+no_connect"))
    )
    (net (code "58") (name "unconnected-(U3-3V3_EN-Pad37)") (class "Default")
      (node (ref "U3") (pin "37") (pinfunction "3V3_EN_37") (pintype "input+no_connect"))
    )
    (net (code "59") (name "unconnected-(U3-GND-PadD2)") (class "Default")
      (node (ref "U3") (pin "D2") (pinfunction "GND_D2") (pintype "bidirectional+no_connect"))
    )
    (net (code "60") (name "unconnected-(U3-GP3-Pad5)") (class "Default")
      (node (ref "U3") (pin "5") (pinfunction "GP3_5") (pintype "bidirectional+no_connect"))
    )
    (net (code "61") (name "unconnected-(U3-GP6-Pad9)") (class "Default")
      (node (ref "U3") (pin "9") (pinfunction "GP6_9") (pintype "bidirectional+no_connect"))
    )
    (net (code "62") (name "unconnected-(U3-GP11-Pad15)") (class "Default")
      (node (ref "U3") (pin "15") (pinfunction "GP11_15") (pintype "bidirectional+no_connect"))
    )
    (net (code "63") (name "unconnected-(U3-GP13-Pad17)") (class "Default")
      (node (ref "U3") (pin "17") (pinfunction "GP13_17") (pintype "bidirectional+no_connect"))
    )
    (net (code "64") (name "unconnected-(U3-GP14-Pad19)") (class "Default")
      (node (ref "U3") (pin "19") (pinfunction "GP14_19") (pintype "bidirectional+no_connect"))
    )
    (net (code "65") (name "unconnected-(U3-SWCLK-PadD1)") (class "Default")
      (node (ref "U3") (pin "D1") (pinfunction "SWCLK_D1") (pintype "input+no_connect"))
    )
    (net (code "66") (name "unconnected-(U3-SWDIO-PadD3)") (class "Default")
      (node (ref "U3") (pin "D3") (pinfunction "SWDIO_D3") (pintype "bidirectional+no_connect"))
    )
    (net (code "67") (name "unconnected-(U3-TP1_GND-PadTP1)") (class "Default")
      (node (ref "U3") (pin "TP1") (pinfunction "TP1_GND_TP1") (pintype "power_in+no_connect"))
    )
    (net (code "68") (name "unconnected-(U3-TP2_USB_DM-PadTP2)") (class "Default")
      (node (ref "U3") (pin "TP2") (pinfunction "TP2_USB_DM_TP2") (pintype "bidirectional+no_connect"))
    )
    (net (code "69") (name "unconnected-(U3-TP3_USB_DP-PadTP3)") (class "Default")
      (node (ref "U3") (pin "TP3") (pinfunction "TP3_USB_DP_TP3") (pintype "bidirectional+no_connect"))
    )
    (net (code "70") (name "unconnected-(U3-TP4_GPIO23{slash}SMPS_PS-PadTP4)") (class "Default")
      (node (ref "U3") (pin "TP4") (pinfunction "TP4_GPIO23/SMPS_PS_TP4") (pintype "passive+no_connect"))
    )
    (net (code "71") (name "unconnected-(U3-TP5_GPIO25{slash}LED-PadTP5)") (class "Default")
      (node (ref "U3") (pin "TP5") (pinfunction "TP5_GPIO25/LED_TP5") (pintype "output+no_connect"))
    )
    (net (code "72") (name "unconnected-(U3-TP6_BOOTSEL-PadTP6)") (class "Default")
      (node (ref "U3") (pin "TP6") (pinfunction "TP6_BOOTSEL_TP6") (pintype "input+no_connect"))
    )
    (net (code "73") (name "unconnected-(U3-USB_SHIELD-PadA)") (class "Default")
      (node (ref "U3") (pin "A") (pinfunction "USB_SHIELD_A") (pintype "power_in+no_connect"))
    )
    (net (code "74") (name "unconnected-(U3-USB_SHIELD-PadB)") (class "Default")
      (node (ref "U3") (pin "B") (pinfunction "USB_SHIELD_B") (pintype "power_in+no_connect"))
    )
    (net (code "75") (name "unconnected-(U3-USB_SHIELD-PadC)") (class "Default")
      (node (ref "U3") (pin "C") (pinfunction "USB_SHIELD_C") (pintype "power_in+no_connect"))
    )
    (net (code "76") (name "unconnected-(U3-USB_SHIELD-PadD)") (class "Default")
      (node (ref "U3") (pin "D") (pinfunction "USB_SHIELD_D") (pintype "power_in+no_connect"))
    )
    (net (code "77") (name "unconnected-(U3-VBUS-Pad40)") (class "Default")
      (node (ref "U3") (pin "40") (pinfunction "VBUS_40") (pintype "power_in+no_connect"))
    )
    (net (code "78") (name "unconnected-(U3-~{RUN}-Pad30)") (class "Default")
      (node (ref "U3") (pin "30") (pinfunction "~{RUN}_30") (pintype "input+no_connect"))
    )
    (net (code "79") (name "unconnected-(U5-NC-Pad4)") (class "Default")
      (node (ref "U5") (pin "4") (pinfunction "NC_4") (pintype "passive+no_connect"))
    )
    (net (code "80") (name "unconnected-(U6-LNA_EN-Pad4)") (class "Default")
      (node (ref "U6") (pin "4") (pinfunction "LNA_EN_4") (pintype "input+no_connect"))
    )
    (net (code "81") (name "unconnected-(U6-SAFEBOOT-Pad3)") (class "Default")
      (node (ref "U6") (pin "3") (pinfunction "SAFEBOOT_3") (pintype "input+no_connect"))
    )
    (net (code "82") (name "unconnected-(U6-TIMEPULS-Pad6)") (class "Default")
      (node (ref "U6") (pin "6") (pinfunction "TIMEPULS_6") (pintype "input+no_connect"))
    )
  )
)
